# Sheet2.net
KiCad netlist of a schematic drawn in Altium Designer
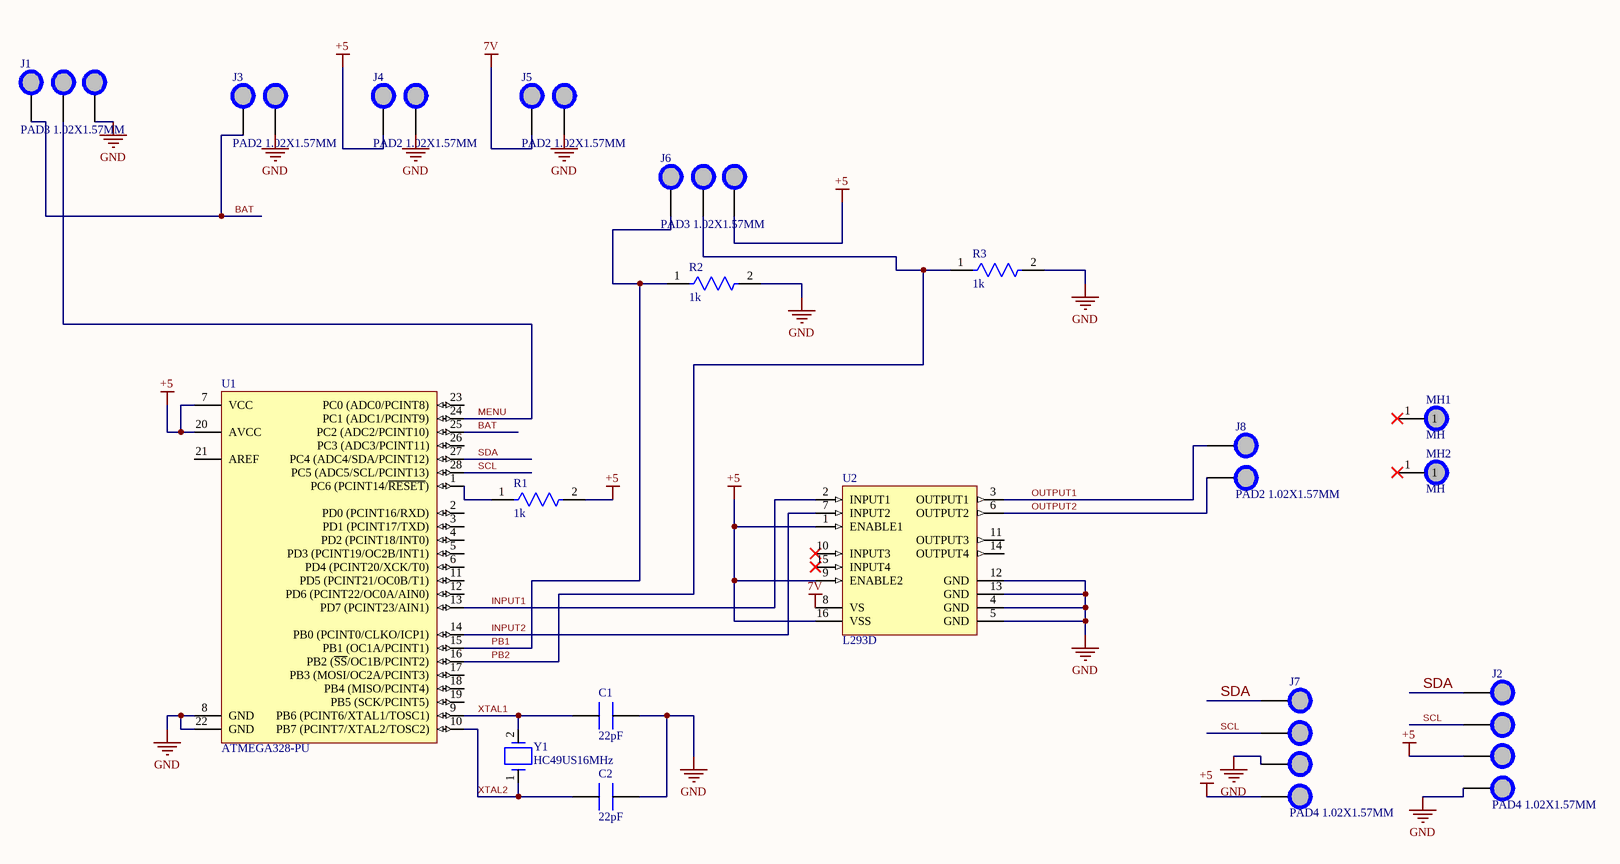
[diagram p0: Sheet2.SchDoc]

(export (version "E")
  (design (tool "Eeschema 10.0.6"))
  (components
    (comp (ref "C1")
      (value "22pF")
      (footprint "Capacitor_22pF")
      (description "Cap Ceramic Suppression X1/Y2 22pF 760VAC/500VAC U2J 10% (8 X 5mm) Radial 10mm 125C Bulk")
      (fields
        (field (name "MANUFACTURER") "Vishay BCcomponents")
        (field (name "MANUFACTURER PART NUMBER") "VY1220K31U2JQ63V0")
      )
      (libsource (lib "Schlib1") (part "VY1220K31U2JQ63V0"))
    )
    (comp (ref "C2")
      (value "22pF")
      (footprint "Capacitor_22pF")
      (description "Cap Ceramic Suppression X1/Y2 22pF 760VAC/500VAC U2J 10% (8 X 5mm) Radial 10mm 125C Bulk")
      (fields
        (field (name "MANUFACTURER") "Vishay BCcomponents")
        (field (name "MANUFACTURER PART NUMBER") "VY1220K31U2JQ63V0")
      )
      (libsource (lib "Schlib1") (part "VY1220K31U2JQ63V0"))
    )
    (comp (ref "J1")
      (value "PAD3 1.02X1.57MM")
      (footprint "PAD3 1.02X1.57MM")
      (libsource (lib "Schlib1") (part "PAD3 1.02X1.57MM"))
    )
    (comp (ref "J2")
      (value "PAD4 1.02X1.57MM")
      (footprint "PAD4 1.02X1.57MM")
      (libsource (lib "Schlib1") (part "PAD4 1.02X1.57MM"))
    )
    (comp (ref "J3")
      (value "PAD2 1.02X1.57MM")
      (footprint "PAD2 1.02X1.57MM")
      (libsource (lib "Schlib1") (part "PAD2 1.02X1.57MM"))
    )
    (comp (ref "J4")
      (value "PAD2 1.02X1.57MM")
      (footprint "PAD2 1.02X1.57MM")
      (libsource (lib "Schlib1") (part "PAD2 1.02X1.57MM"))
    )
    (comp (ref "J5")
      (value "PAD2 1.02X1.57MM")
      (footprint "PAD2 1.02X1.57MM")
      (libsource (lib "Schlib1") (part "PAD2 1.02X1.57MM"))
    )
    (comp (ref "J6")
      (value "PAD3 1.02X1.57MM")
      (footprint "PAD3 1.02X1.57MM")
      (libsource (lib "Schlib1") (part "PAD3 1.02X1.57MM"))
    )
    (comp (ref "J7")
      (value "PAD4 1.02X1.57MM")
      (footprint "PAD4 1.02X1.57MM")
      (libsource (lib "Schlib1") (part "PAD4 1.02X1.57MM"))
    )
    (comp (ref "J8")
      (value "PAD2 1.02X1.57MM")
      (footprint "PAD2 1.02X1.57MM")
      (libsource (lib "Schlib1") (part "PAD2 1.02X1.57MM"))
    )
    (comp (ref "MH1") (value "MH") (footprint "MH") (libsource (lib "Schlib1") (part "MH")))
    (comp (ref "MH2") (value "MH") (footprint "MH") (libsource (lib "Schlib1") (part "MH")))
    (comp (ref "R1")
      (value "1k")
      (footprint "resistor")
      (description "MRS25 Series Axial Thin Film Resistor 1kOhms +/-1% 0.6W +/-50ppm/degC")
      (fields
        (field (name "MANUFACTURER") "Vishay")
        (field (name "MANUFACTURER PART NUMBER") "MRS25000C1001FCT00")
      )
      (libsource (lib "Schlib1") (part "MRS25000C1001FCT00"))
    )
    (comp (ref "R2")
      (value "1k")
      (footprint "resistor")
      (description "MRS25 Series Axial Thin Film Resistor 1kOhms +/-1% 0.6W +/-50ppm/degC")
      (fields
        (field (name "MANUFACTURER") "Vishay")
        (field (name "MANUFACTURER PART NUMBER") "MRS25000C1001FCT00")
      )
      (libsource (lib "Schlib1") (part "MRS25000C1001FCT00"))
    )
    (comp (ref "R3")
      (value "1k")
      (footprint "resistor")
      (description "MRS25 Series Axial Thin Film Resistor 1kOhms +/-1% 0.6W +/-50ppm/degC")
      (fields
        (field (name "MANUFACTURER") "Vishay")
        (field (name "MANUFACTURER PART NUMBER") "MRS25000C1001FCT00")
      )
      (libsource (lib "Schlib1") (part "MRS25000C1001FCT00"))
    )
    (comp (ref "U1")
      (value "ATMEGA328-PU")
      (footprint "DIP28 7.62MM")
      (description "ATmega Series 32 kB Flash 2 kB SRAM 20 MHz 8-Bit Microcontroller - DIP-28")
      (fields (field (name "MANUFACTURER") "Microchip"))
      (libsource (lib "Schlib1") (part "ATMEGA328-PU"))
    )
    (comp (ref "U2")
      (value "L293D")
      (footprint "DIP16")
      (description "IC MOTOR DRIVER PAR 16-DIP")
      (fields (field (name "MANUFACTURER") "STMicroelectronics"))
      (libsource (lib "Schlib1") (part "L293D"))
    )
    (comp (ref "Y1")
      (value "HC49US16MHz")
      (footprint "HC49US16MHz")
      (fields
        (field (name "MANUFACTURER") "Citizen")
        (field (name "MANUFACTURER PART NUMBER") "HC49US16.384MABJ-UB")
      )
      (libsource (lib "Schlib1") (part "HC49US16.384MABJ-UB"))
    )
  )
  (nets
    (net (code "1") (name "+5") (class "Default")
      (node (ref "J2") (pin "3") (pinfunction "3_3") (pintype "passive"))
      (node (ref "J4") (pin "1") (pinfunction "1_1") (pintype "passive"))
      (node (ref "J6") (pin "3") (pinfunction "3_3") (pintype "passive"))
      (node (ref "J7") (pin "4") (pinfunction "4_4") (pintype "passive"))
      (node (ref "R1") (pin "2") (pinfunction "2_2") (pintype "passive"))
      (node (ref "U1") (pin "20") (pinfunction "AVCC_20") (pintype "power_in"))
      (node (ref "U1") (pin "7") (pinfunction "VCC_7") (pintype "power_in"))
      (node (ref "U2") (pin "1") (pinfunction "ENABLE1_1") (pintype "input"))
      (node (ref "U2") (pin "16") (pinfunction "VSS_16") (pintype "passive"))
      (node (ref "U2") (pin "9") (pinfunction "ENABLE2_9") (pintype "input"))
    )
    (net (code "2") (name "/BAT") (class "Default")
      (node (ref "J1") (pin "1") (pinfunction "1_1") (pintype "passive"))
      (node (ref "J3") (pin "1") (pinfunction "1_1") (pintype "passive"))
      (node (ref "U1") (pin "25") (pinfunction "PC2_(ADC2/PCINT10)_25") (pintype "bidirectional"))
    )
    (net (code "3") (name "/INPUT1") (class "Default")
      (node (ref "U1") (pin "13") (pinfunction "PD7_(PCINT23/AIN1)_13") (pintype "bidirectional"))
      (node (ref "U2") (pin "2") (pinfunction "INPUT1_2") (pintype "input"))
    )
    (net (code "4") (name "/INPUT2") (class "Default")
      (node (ref "U1") (pin "14") (pinfunction "PB0_(PCINT0/CLKO/ICP1)_14") (pintype "bidirectional"))
      (node (ref "U2") (pin "7") (pinfunction "INPUT2_7") (pintype "input"))
    )
    (net (code "5") (name "/MENU") (class "Default")
      (node (ref "J1") (pin "2") (pinfunction "2_2") (pintype "passive"))
      (node (ref "U1") (pin "24") (pinfunction "PC1_(ADC1/PCINT9)_24") (pintype "bidirectional"))
    )
    (net (code "6") (name "/OUTPUT1") (class "Default")
      (node (ref "J8") (pin "1") (pinfunction "1_1") (pintype "passive"))
      (node (ref "U2") (pin "3") (pinfunction "OUTPUT1_3") (pintype "output"))
    )
    (net (code "7") (name "/OUTPUT2") (class "Default")
      (node (ref "J8") (pin "2") (pinfunction "2_2") (pintype "passive"))
      (node (ref "U2") (pin "6") (pinfunction "OUTPUT2_6") (pintype "output"))
    )
    (net (code "8") (name "/PB1") (class "Default")
      (node (ref "J6") (pin "1") (pinfunction "1_1") (pintype "passive"))
      (node (ref "R2") (pin "1") (pinfunction "1_1") (pintype "passive"))
      (node (ref "U1") (pin "15") (pinfunction "PB1_(OC1A/PCINT1)_15") (pintype "bidirectional"))
    )
    (net (code "9") (name "/PB2") (class "Default")
      (node (ref "J6") (pin "2") (pinfunction "2_2") (pintype "passive"))
      (node (ref "R3") (pin "1") (pinfunction "1_1") (pintype "passive"))
      (node (ref "U1") (pin "16") (pinfunction "PB2_(~{SS}/OC1B/PCINT2)_16") (pintype "bidirectional"))
    )
    (net (code "10") (name "/SCL") (class "Default")
      (node (ref "J2") (pin "2") (pinfunction "2_2") (pintype "passive"))
      (node (ref "J7") (pin "2") (pinfunction "2_2") (pintype "passive"))
      (node (ref "U1") (pin "28") (pinfunction "PC5_(ADC5/SCL/PCINT13)_28") (pintype "bidirectional"))
    )
    (net (code "11") (name "/SDA") (class "Default")
      (node (ref "J2") (pin "1") (pinfunction "1_1") (pintype "passive"))
      (node (ref "J7") (pin "1") (pinfunction "1_1") (pintype "passive"))
      (node (ref "U1") (pin "27") (pinfunction "PC4_(ADC4/SDA/PCINT12)_27") (pintype "bidirectional"))
    )
    (net (code "12") (name "/XTAL1") (class "Default")
      (node (ref "C1") (pin "1") (pinfunction "1_1") (pintype "passive"))
      (node (ref "U1") (pin "9") (pinfunction "PB6_(PCINT6/XTAL1/TOSC1)_9") (pintype "bidirectional"))
      (node (ref "Y1") (pin "2") (pinfunction "2_2") (pintype "passive"))
    )
    (net (code "13") (name "/XTAL2") (class "Default")
      (node (ref "C2") (pin "1") (pinfunction "1_1") (pintype "passive"))
      (node (ref "U1") (pin "10") (pinfunction "PB7_(PCINT7/XTAL2/TOSC2)_10") (pintype "bidirectional"))
      (node (ref "Y1") (pin "1") (pinfunction "1_1") (pintype "passive"))
    )
    (net (code "14") (name "7V") (class "Default")
      (node (ref "J5") (pin "1") (pinfunction "1_1") (pintype "passive"))
      (node (ref "U2") (pin "8") (pinfunction "VS_8") (pintype "passive"))
    )
    (net (code "15") (name "GND") (class "Default")
      (node (ref "C1") (pin "2") (pinfunction "2_2") (pintype "passive"))
      (node (ref "C2") (pin "2") (pinfunction "2_2") (pintype "passive"))
      (node (ref "J1") (pin "3") (pinfunction "3_3") (pintype "passive"))
      (node (ref "J2") (pin "4") (pinfunction "4_4") (pintype "passive"))
      (node (ref "J3") (pin "2") (pinfunction "2_2") (pintype "passive"))
      (node (ref "J4") (pin "2") (pinfunction "2_2") (pintype "passive"))
      (node (ref "J5") (pin "2") (pinfunction "2_2") (pintype "passive"))
      (node (ref "J7") (pin "3") (pinfunction "3_3") (pintype "passive"))
      (node (ref "R2") (pin "2") (pinfunction "2_2") (pintype "passive"))
      (node (ref "R3") (pin "2") (pinfunction "2_2") (pintype "passive"))
      (node (ref "U1") (pin "22") (pinfunction "GND_22") (pintype "power_in"))
      (node (ref "U1") (pin "8") (pinfunction "GND_8") (pintype "power_in"))
      (node (ref "U2") (pin "12") (pinfunction "GND_12") (pintype "passive"))
      (node (ref "U2") (pin "13") (pinfunction "GND_13") (pintype "passive"))
      (node (ref "U2") (pin "4") (pinfunction "GND_4") (pintype "passive"))
      (node (ref "U2") (pin "5") (pinfunction "GND_5") (pintype "passive"))
    )
    (net (code "16") (name "Net-(U1-PC6_(PCINT14{slash}~{RESET}))") (class "Default")
      (node (ref "R1") (pin "1") (pinfunction "1_1") (pintype "passive"))
      (node (ref "U1") (pin "1") (pinfunction "PC6_(PCINT14/~{RESET})_1") (pintype "bidirectional"))
    )
    (net (code "17") (name "unconnected-(MH1-Pad1)") (class "Default")
      (node (ref "MH1") (pin "1") (pinfunction "1_1") (pintype "passive+no_connect"))
    )
    (net (code "18") (name "unconnected-(MH2-Pad1)") (class "Default")
      (node (ref "MH2") (pin "1") (pinfunction "1_1") (pintype "passive+no_connect"))
    )
    (net (code "19") (name "unconnected-(U1-AREF-Pad21)") (class "Default")
      (node (ref "U1") (pin "21") (pinfunction "AREF_21") (pintype "power_in"))
    )
    (net (code "20") (name "unconnected-(U1-PB3_(MOSI{slash}OC2A{slash}PCINT3)-Pad17)") (class "Default")
      (node (ref "U1") (pin "17") (pinfunction "PB3_(MOSI/OC2A/PCINT3)_17") (pintype "bidirectional"))
    )
    (net (code "21") (name "unconnected-(U1-PB4_(MISO{slash}PCINT4)-Pad18)") (class "Default")
      (node (ref "U1") (pin "18") (pinfunction "PB4_(MISO/PCINT4)_18") (pintype "bidirectional"))
    )
    (net (code "22") (name "unconnected-(U1-PB5_(SCK{slash}PCINT5)-Pad19)") (class "Default")
      (node (ref "U1") (pin "19") (pinfunction "PB5_(SCK/PCINT5)_19") (pintype "bidirectional"))
    )
    (net (code "23") (name "unconnected-(U1-PC0_(ADC0{slash}PCINT8)-Pad23)") (class "Default")
      (node (ref "U1") (pin "23") (pinfunction "PC0_(ADC0/PCINT8)_23") (pintype "bidirectional"))
    )
    (net (code "24") (name "unconnected-(U1-PC3_(ADC3{slash}PCINT11)-Pad26)") (class "Default")
      (node (ref "U1") (pin "26") (pinfunction "PC3_(ADC3/PCINT11)_26") (pintype "bidirectional"))
    )
    (net (code "25") (name "unconnected-(U1-PD0_(PCINT16{slash}RXD)-Pad2)") (class "Default")
      (node (ref "U1") (pin "2") (pinfunction "PD0_(PCINT16/RXD)_2") (pintype "bidirectional"))
    )
    (net (code "26") (name "unconnected-(U1-PD1_(PCINT17{slash}TXD)-Pad3)") (class "Default")
      (node (ref "U1") (pin "3") (pinfunction "PD1_(PCINT17/TXD)_3") (pintype "bidirectional"))
    )
    (net (code "27") (name "unconnected-(U1-PD2_(PCINT18{slash}INT0)-Pad4)") (class "Default")
      (node (ref "U1") (pin "4") (pinfunction "PD2_(PCINT18/INT0)_4") (pintype "bidirectional"))
    )
    (net (code "28") (name "unconnected-(U1-PD3_(PCINT19{slash}OC2B{slash}INT1)-Pad5)") (class "Default")
      (node (ref "U1") (pin "5") (pinfunction "PD3_(PCINT19/OC2B/INT1)_5") (pintype "bidirectional"))
    )
    (net (code "29") (name "unconnected-(U1-PD4_(PCINT20{slash}XCK{slash}T0)-Pad6)") (class "Default")
      (node (ref "U1") (pin "6") (pinfunction "PD4_(PCINT20/XCK/T0)_6") (pintype "bidirectional"))
    )
    (net (code "30") (name "unconnected-(U1-PD5_(PCINT21{slash}OC0B{slash}T1)-Pad11)") (class "Default")
      (node (ref "U1") (pin "11") (pinfunction "PD5_(PCINT21/OC0B/T1)_11") (pintype "bidirectional"))
    )
    (net (code "31") (name "unconnected-(U1-PD6_(PCINT22{slash}OC0A{slash}AIN0)-Pad12)") (class "Default")
      (node (ref "U1") (pin "12") (pinfunction "PD6_(PCINT22/OC0A/AIN0)_12") (pintype "bidirectional"))
    )
    (net (code "32") (name "unconnected-(U2-INPUT3-Pad10)") (class "Default")
      (node (ref "U2") (pin "10") (pinfunction "INPUT3_10") (pintype "input+no_connect"))
    )
    (net (code "33") (name "unconnected-(U2-INPUT4-Pad15)") (class "Default")
      (node (ref "U2") (pin "15") (pinfunction "INPUT4_15") (pintype "input+no_connect"))
    )
    (net (code "34") (name "unconnected-(U2-OUTPUT3-Pad11)") (class "Default")
      (node (ref "U2") (pin "11") (pinfunction "OUTPUT3_11") (pintype "output"))
    )
    (net (code "35") (name "unconnected-(U2-OUTPUT4-Pad14)") (class "Default")
      (node (ref "U2") (pin "14") (pinfunction "OUTPUT4_14") (pintype "output"))
    )
  )
)
